# USB-C_BREAKOUT_COMPONENTS.net
KiCad netlist of a schematic drawn in Altium Designer
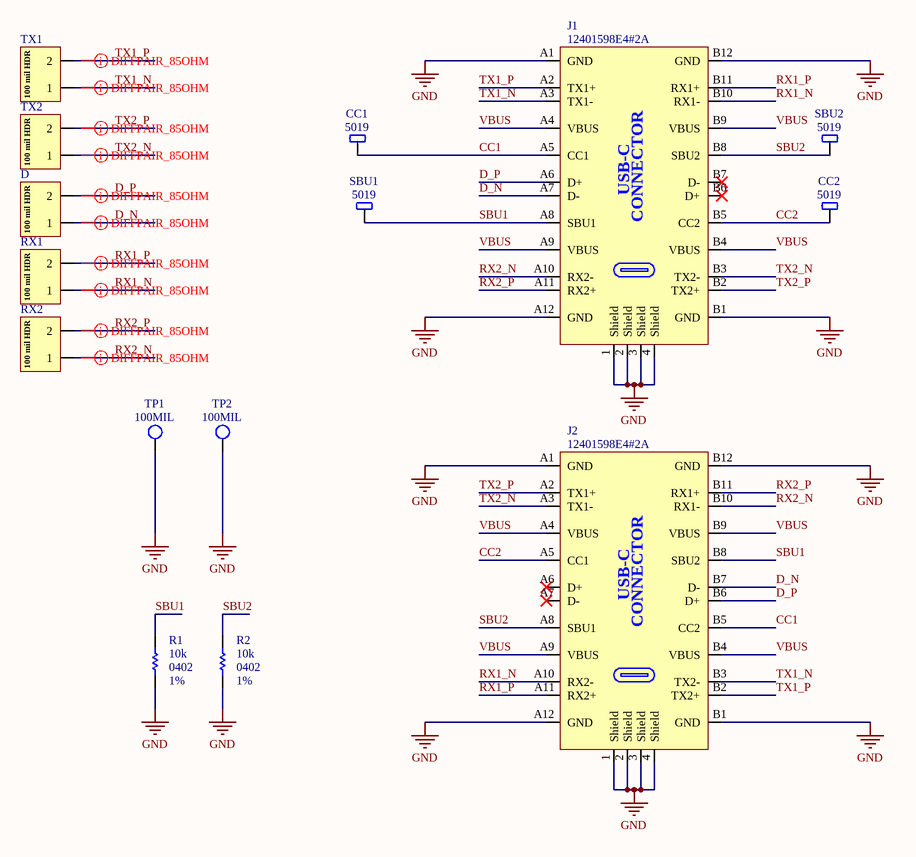
[diagram p0: USB-C_BREAKOUT_COMPONENTS.SchDoc]

(export (version "E")
  (design (tool "Eeschema 10.0.6"))
  (components
    (comp (ref "CC1")
      (value "5019")
      (footprint "GRAMS_MASTER_LIB_PCB:TPO_SMD_5019")
      (description "TPO - PC TEST POINT MINI - SMD")
      (fields
        (field (name "CREATEDBY/DATE") "Olivier Bernard / 5/12/2017")
        (field (name "VERIFIEDBY") "Caroline Paulin / 5 juillet 2018")
      )
      (libsource (lib "GRAMS_MASTER_LIB_SCH") (part "TPO_SMD_5019"))
    )
    (comp (ref "CC2")
      (value "5019")
      (footprint "GRAMS_MASTER_LIB_PCB:TPO_SMD_5019")
      (description "TPO - PC TEST POINT MINI - SMD")
      (fields
        (field (name "CREATEDBY/DATE") "Olivier Bernard / 5/12/2017")
        (field (name "VERIFIEDBY") "Caroline Paulin / 5 juillet 2018")
      )
      (libsource (lib "GRAMS_MASTER_LIB_SCH") (part "TPO_SMD_5019"))
    )
    (comp (ref "D")
      (value "TS-102-G-A")
      (footprint "GRAMS_MASTER_LIB_PCB:CON_HDR_TS-102-G-A")
      (description "CON - HDR 2 position 0.100\" - TH")
      (fields
        (field (name "CREATEDBY/DATE") "Joel Lemay 2018-06-19")
        (field (name "VERIFIEDBY") "Caroline Paulin - 10 sept 2018")
      )
      (libsource (lib "GRAMS_MASTER_LIB_SCH") (part "CON_HDR_TS-102-G-A"))
    )
    (comp (ref "J1")
      (value "12401598E4#2A")
      (footprint "CON_USB_3.2_TypeC_12401598E4#2A")
      (description "CON_USB - USB 3.2 Gen 2 (USB 3.1 Gen 2, Superspeed + (USB 3.1)) 24 pos Receptacle - R/A")
      (fields
        (field (name "CREATEDBY/DATE") "Louis-Daniel Gaulin / 07-04-2021")
        (field (name "VERIFIEDBY") "Philippe Arsenault/2021-04-08")
      )
      (libsource (lib "SWARMUS_LIB") (part "CON_USB_3.2_TypeC_12401598E4#2A"))
    )
    (comp (ref "J2")
      (value "12401598E4#2A")
      (footprint "CON_USB_3.2_TypeC_12401598E4#2A")
      (description "CON_USB - USB 3.2 Gen 2 (USB 3.1 Gen 2, Superspeed + (USB 3.1)) 24 pos Receptacle - R/A")
      (fields
        (field (name "CREATEDBY/DATE") "Louis-Daniel Gaulin / 07-04-2021")
        (field (name "VERIFIEDBY") "Philippe Arsenault/2021-04-08")
      )
      (libsource (lib "SWARMUS_LIB") (part "CON_USB_3.2_TypeC_12401598E4#2A"))
    )
    (comp (ref "R1")
      (value "10k")
      (footprint "GRAMS_MASTER_LIB_PCB:RES_0402")
      (description "RES - 10K OHMS 1% 1/16W - 0402")
      (fields
        (field (name "TOLERANCE") "1%")
        (field (name "PACKAGE") "0402")
        (field (name "Comment") "RC0402FR-0710KL")
        (field (name "CREATEDBY/DATE") "Nicolas V. (2018-11-20)")
        (field (name "VERIFIEDBY") "Nicolas V. (2018-11-20)")
      )
      (libsource (lib "GRAMS_MASTER_LIB_SCH") (part "RES_RC0402FR-0710KL"))
    )
    (comp (ref "R2")
      (value "10k")
      (footprint "GRAMS_MASTER_LIB_PCB:RES_0402")
      (description "RES - 10K OHMS 1% 1/16W - 0402")
      (fields
        (field (name "TOLERANCE") "1%")
        (field (name "PACKAGE") "0402")
        (field (name "Comment") "RC0402FR-0710KL")
        (field (name "CREATEDBY/DATE") "Nicolas V. (2018-11-20)")
        (field (name "VERIFIEDBY") "Nicolas V. (2018-11-20)")
      )
      (libsource (lib "GRAMS_MASTER_LIB_SCH") (part "RES_RC0402FR-0710KL"))
    )
    (comp (ref "RX1")
      (value "TS-102-G-A")
      (footprint "GRAMS_MASTER_LIB_PCB:CON_HDR_TS-102-G-A")
      (description "CON - HDR 2 position 0.100\" - TH")
      (fields
        (field (name "CREATEDBY/DATE") "Joel Lemay 2018-06-19")
        (field (name "VERIFIEDBY") "Caroline Paulin - 10 sept 2018")
      )
      (libsource (lib "GRAMS_MASTER_LIB_SCH") (part "CON_HDR_TS-102-G-A"))
    )
    (comp (ref "RX2")
      (value "TS-102-G-A")
      (footprint "GRAMS_MASTER_LIB_PCB:CON_HDR_TS-102-G-A")
      (description "CON - HDR 2 position 0.100\" - TH")
      (fields
        (field (name "CREATEDBY/DATE") "Joel Lemay 2018-06-19")
        (field (name "VERIFIEDBY") "Caroline Paulin - 10 sept 2018")
      )
      (libsource (lib "GRAMS_MASTER_LIB_SCH") (part "CON_HDR_TS-102-G-A"))
    )
    (comp (ref "SBU1")
      (value "5019")
      (footprint "GRAMS_MASTER_LIB_PCB:TPO_SMD_5019")
      (description "TPO - PC TEST POINT MINI - SMD")
      (fields
        (field (name "CREATEDBY/DATE") "Olivier Bernard / 5/12/2017")
        (field (name "VERIFIEDBY") "Caroline Paulin / 5 juillet 2018")
      )
      (libsource (lib "GRAMS_MASTER_LIB_SCH") (part "TPO_SMD_5019"))
    )
    (comp (ref "SBU2")
      (value "5019")
      (footprint "GRAMS_MASTER_LIB_PCB:TPO_SMD_5019")
      (description "TPO - PC TEST POINT MINI - SMD")
      (fields
        (field (name "CREATEDBY/DATE") "Olivier Bernard / 5/12/2017")
        (field (name "VERIFIEDBY") "Caroline Paulin / 5 juillet 2018")
      )
      (libsource (lib "GRAMS_MASTER_LIB_SCH") (part "TPO_SMD_5019"))
    )
    (comp (ref "TP1")
      (value "100MIL")
      (footprint "grams_master_lib_pcb:TPO_TH_ROUND_100MIL")
      (description "TPO - TEST POINT ROUND TH  - 100MIL")
      (fields
        (field (name "CREATEDBY/DATE") "Louis-Daniel Gaulin/ 14/01/2020")
        (field (name "VERIFIEDBY") "C.Paulin - 21/01/2020")
      )
      (libsource (lib "GRAMS_MASTER_LIB_SCH") (part "TPO_TH_ROUND_100MIL"))
    )
    (comp (ref "TP2")
      (value "100MIL")
      (footprint "grams_master_lib_pcb:TPO_TH_ROUND_100MIL")
      (description "TPO - TEST POINT ROUND TH  - 100MIL")
      (fields
        (field (name "CREATEDBY/DATE") "Louis-Daniel Gaulin/ 14/01/2020")
        (field (name "VERIFIEDBY") "C.Paulin - 21/01/2020")
      )
      (libsource (lib "GRAMS_MASTER_LIB_SCH") (part "TPO_TH_ROUND_100MIL"))
    )
    (comp (ref "TX1")
      (value "TS-102-G-A")
      (footprint "GRAMS_MASTER_LIB_PCB:CON_HDR_TS-102-G-A")
      (description "CON - HDR 2 position 0.100\" - TH")
      (fields
        (field (name "CREATEDBY/DATE") "Joel Lemay 2018-06-19")
        (field (name "VERIFIEDBY") "Caroline Paulin - 10 sept 2018")
      )
      (libsource (lib "GRAMS_MASTER_LIB_SCH") (part "CON_HDR_TS-102-G-A"))
    )
    (comp (ref "TX2")
      (value "TS-102-G-A")
      (footprint "GRAMS_MASTER_LIB_PCB:CON_HDR_TS-102-G-A")
      (description "CON - HDR 2 position 0.100\" - TH")
      (fields
        (field (name "CREATEDBY/DATE") "Joel Lemay 2018-06-19")
        (field (name "VERIFIEDBY") "Caroline Paulin - 10 sept 2018")
      )
      (libsource (lib "GRAMS_MASTER_LIB_SCH") (part "CON_HDR_TS-102-G-A"))
    )
  )
  (nets
    (net (code "1") (name "/CC1") (class "Default")
      (node (ref "CC1") (pin "1") (pinfunction "1_1") (pintype "passive"))
      (node (ref "J1") (pin "A5") (pinfunction "CC1_A5") (pintype "passive"))
      (node (ref "J2") (pin "B5") (pinfunction "CC2_B5") (pintype "passive"))
    )
    (net (code "2") (name "/CC2") (class "Default")
      (node (ref "CC2") (pin "1") (pinfunction "1_1") (pintype "passive"))
      (node (ref "J1") (pin "B5") (pinfunction "CC2_B5") (pintype "passive"))
      (node (ref "J2") (pin "A5") (pinfunction "CC1_A5") (pintype "passive"))
    )
    (net (code "3") (name "/D_N") (class "Default")
      (node (ref "D") (pin "1") (pinfunction "1_1") (pintype "passive"))
      (node (ref "J1") (pin "A7") (pinfunction "D-_A7") (pintype "passive"))
      (node (ref "J2") (pin "B7") (pinfunction "D-_B7") (pintype "passive"))
    )
    (net (code "4") (name "/D_P") (class "Default")
      (node (ref "D") (pin "2") (pinfunction "2_2") (pintype "passive"))
      (node (ref "J1") (pin "A6") (pinfunction "D+_A6") (pintype "passive"))
      (node (ref "J2") (pin "B6") (pinfunction "D+_B6") (pintype "passive"))
    )
    (net (code "5") (name "/RX1_N") (class "Default")
      (node (ref "J1") (pin "B10") (pinfunction "RX1-_B10") (pintype "passive"))
      (node (ref "J2") (pin "A10") (pinfunction "RX2-_A10") (pintype "passive"))
      (node (ref "RX1") (pin "1") (pinfunction "1_1") (pintype "passive"))
    )
    (net (code "6") (name "/RX1_P") (class "Default")
      (node (ref "J1") (pin "B11") (pinfunction "RX1+_B11") (pintype "passive"))
      (node (ref "J2") (pin "A11") (pinfunction "RX2+_A11") (pintype "passive"))
      (node (ref "RX1") (pin "2") (pinfunction "2_2") (pintype "passive"))
    )
    (net (code "7") (name "/RX2_N") (class "Default")
      (node (ref "J1") (pin "A10") (pinfunction "RX2-_A10") (pintype "passive"))
      (node (ref "J2") (pin "B10") (pinfunction "RX1-_B10") (pintype "passive"))
      (node (ref "RX2") (pin "1") (pinfunction "1_1") (pintype "passive"))
    )
    (net (code "8") (name "/RX2_P") (class "Default")
      (node (ref "J1") (pin "A11") (pinfunction "RX2+_A11") (pintype "passive"))
      (node (ref "J2") (pin "B11") (pinfunction "RX1+_B11") (pintype "passive"))
      (node (ref "RX2") (pin "2") (pinfunction "2_2") (pintype "passive"))
    )
    (net (code "9") (name "/SBU1") (class "Default")
      (node (ref "J1") (pin "A8") (pinfunction "SBU1_A8") (pintype "passive"))
      (node (ref "J2") (pin "B8") (pinfunction "SBU2_B8") (pintype "passive"))
      (node (ref "R1") (pin "1") (pinfunction "1_1") (pintype "passive"))
      (node (ref "SBU1") (pin "1") (pinfunction "1_1") (pintype "passive"))
    )
    (net (code "10") (name "/SBU2") (class "Default")
      (node (ref "J1") (pin "B8") (pinfunction "SBU2_B8") (pintype "passive"))
      (node (ref "J2") (pin "A8") (pinfunction "SBU1_A8") (pintype "passive"))
      (node (ref "R2") (pin "1") (pinfunction "1_1") (pintype "passive"))
      (node (ref "SBU2") (pin "1") (pinfunction "1_1") (pintype "passive"))
    )
    (net (code "11") (name "/TX1_N") (class "Default")
      (node (ref "J1") (pin "A3") (pinfunction "TX1-_A3") (pintype "passive"))
      (node (ref "J2") (pin "B3") (pinfunction "TX2-_B3") (pintype "passive"))
      (node (ref "TX1") (pin "1") (pinfunction "1_1") (pintype "passive"))
    )
    (net (code "12") (name "/TX1_P") (class "Default")
      (node (ref "J1") (pin "A2") (pinfunction "TX1+_A2") (pintype "passive"))
      (node (ref "J2") (pin "B2") (pinfunction "TX2+_B2") (pintype "passive"))
      (node (ref "TX1") (pin "2") (pinfunction "2_2") (pintype "passive"))
    )
    (net (code "13") (name "/TX2_N") (class "Default")
      (node (ref "J1") (pin "B3") (pinfunction "TX2-_B3") (pintype "passive"))
      (node (ref "J2") (pin "A3") (pinfunction "TX1-_A3") (pintype "passive"))
      (node (ref "TX2") (pin "1") (pinfunction "1_1") (pintype "passive"))
    )
    (net (code "14") (name "/TX2_P") (class "Default")
      (node (ref "J1") (pin "B2") (pinfunction "TX2+_B2") (pintype "passive"))
      (node (ref "J2") (pin "A2") (pinfunction "TX1+_A2") (pintype "passive"))
      (node (ref "TX2") (pin "2") (pinfunction "2_2") (pintype "passive"))
    )
    (net (code "15") (name "/VBUS") (class "Default")
      (node (ref "J1") (pin "A4") (pinfunction "VBUS_A4") (pintype "passive"))
      (node (ref "J1") (pin "A9") (pinfunction "VBUS_A9") (pintype "passive"))
      (node (ref "J1") (pin "B4") (pinfunction "VBUS_B4") (pintype "passive"))
      (node (ref "J1") (pin "B9") (pinfunction "VBUS_B9") (pintype "passive"))
      (node (ref "J2") (pin "A4") (pinfunction "VBUS_A4") (pintype "passive"))
      (node (ref "J2") (pin "A9") (pinfunction "VBUS_A9") (pintype "passive"))
      (node (ref "J2") (pin "B4") (pinfunction "VBUS_B4") (pintype "passive"))
      (node (ref "J2") (pin "B9") (pinfunction "VBUS_B9") (pintype "passive"))
    )
    (net (code "16") (name "GND") (class "Default")
      (node (ref "J1") (pin "1") (pinfunction "Shield_1") (pintype "passive"))
      (node (ref "J1") (pin "2") (pinfunction "Shield_2") (pintype "passive"))
      (node (ref "J1") (pin "3") (pinfunction "Shield_3") (pintype "passive"))
      (node (ref "J1") (pin "4") (pinfunction "Shield_4") (pintype "passive"))
      (node (ref "J1") (pin "A1") (pinfunction "GND_A1") (pintype "passive"))
      (node (ref "J1") (pin "A12") (pinfunction "GND_A12") (pintype "passive"))
      (node (ref "J1") (pin "B1") (pinfunction "GND_B1") (pintype "passive"))
      (node (ref "J1") (pin "B12") (pinfunction "GND_B12") (pintype "passive"))
      (node (ref "J2") (pin "1") (pinfunction "Shield_1") (pintype "passive"))
      (node (ref "J2") (pin "2") (pinfunction "Shield_2") (pintype "passive"))
      (node (ref "J2") (pin "3") (pinfunction "Shield_3") (pintype "passive"))
      (node (ref "J2") (pin "4") (pinfunction "Shield_4") (pintype "passive"))
      (node (ref "J2") (pin "A1") (pinfunction "GND_A1") (pintype "passive"))
      (node (ref "J2") (pin "A12") (pinfunction "GND_A12") (pintype "passive"))
      (node (ref "J2") (pin "B1") (pinfunction "GND_B1") (pintype "passive"))
      (node (ref "J2") (pin "B12") (pinfunction "GND_B12") (pintype "passive"))
      (node (ref "R1") (pin "2") (pinfunction "2_2") (pintype "passive"))
      (node (ref "R2") (pin "2") (pinfunction "2_2") (pintype "passive"))
      (node (ref "TP1") (pin "1") (pinfunction "1_1") (pintype "passive"))
      (node (ref "TP2") (pin "1") (pinfunction "1_1") (pintype "passive"))
    )
    (net (code "17") (name "unconnected-(J1-D+-PadB6)") (class "Default")
      (node (ref "J1") (pin "B6") (pinfunction "D+_B6") (pintype "passive+no_connect"))
    )
    (net (code "18") (name "unconnected-(J1-D--PadB7)") (class "Default")
      (node (ref "J1") (pin "B7") (pinfunction "D-_B7") (pintype "passive+no_connect"))
    )
    (net (code "19") (name "unconnected-(J2-D+-PadA6)") (class "Default")
      (node (ref "J2") (pin "A6") (pinfunction "D+_A6") (pintype "passive+no_connect"))
    )
    (net (code "20") (name "unconnected-(J2-D--PadA7)") (class "Default")
      (node (ref "J2") (pin "A7") (pinfunction "D-_A7") (pintype "passive+no_connect"))
    )
  )
)
